# TempControl_PSU.net
KiCad netlist of a schematic drawn in EasyEDA Pro
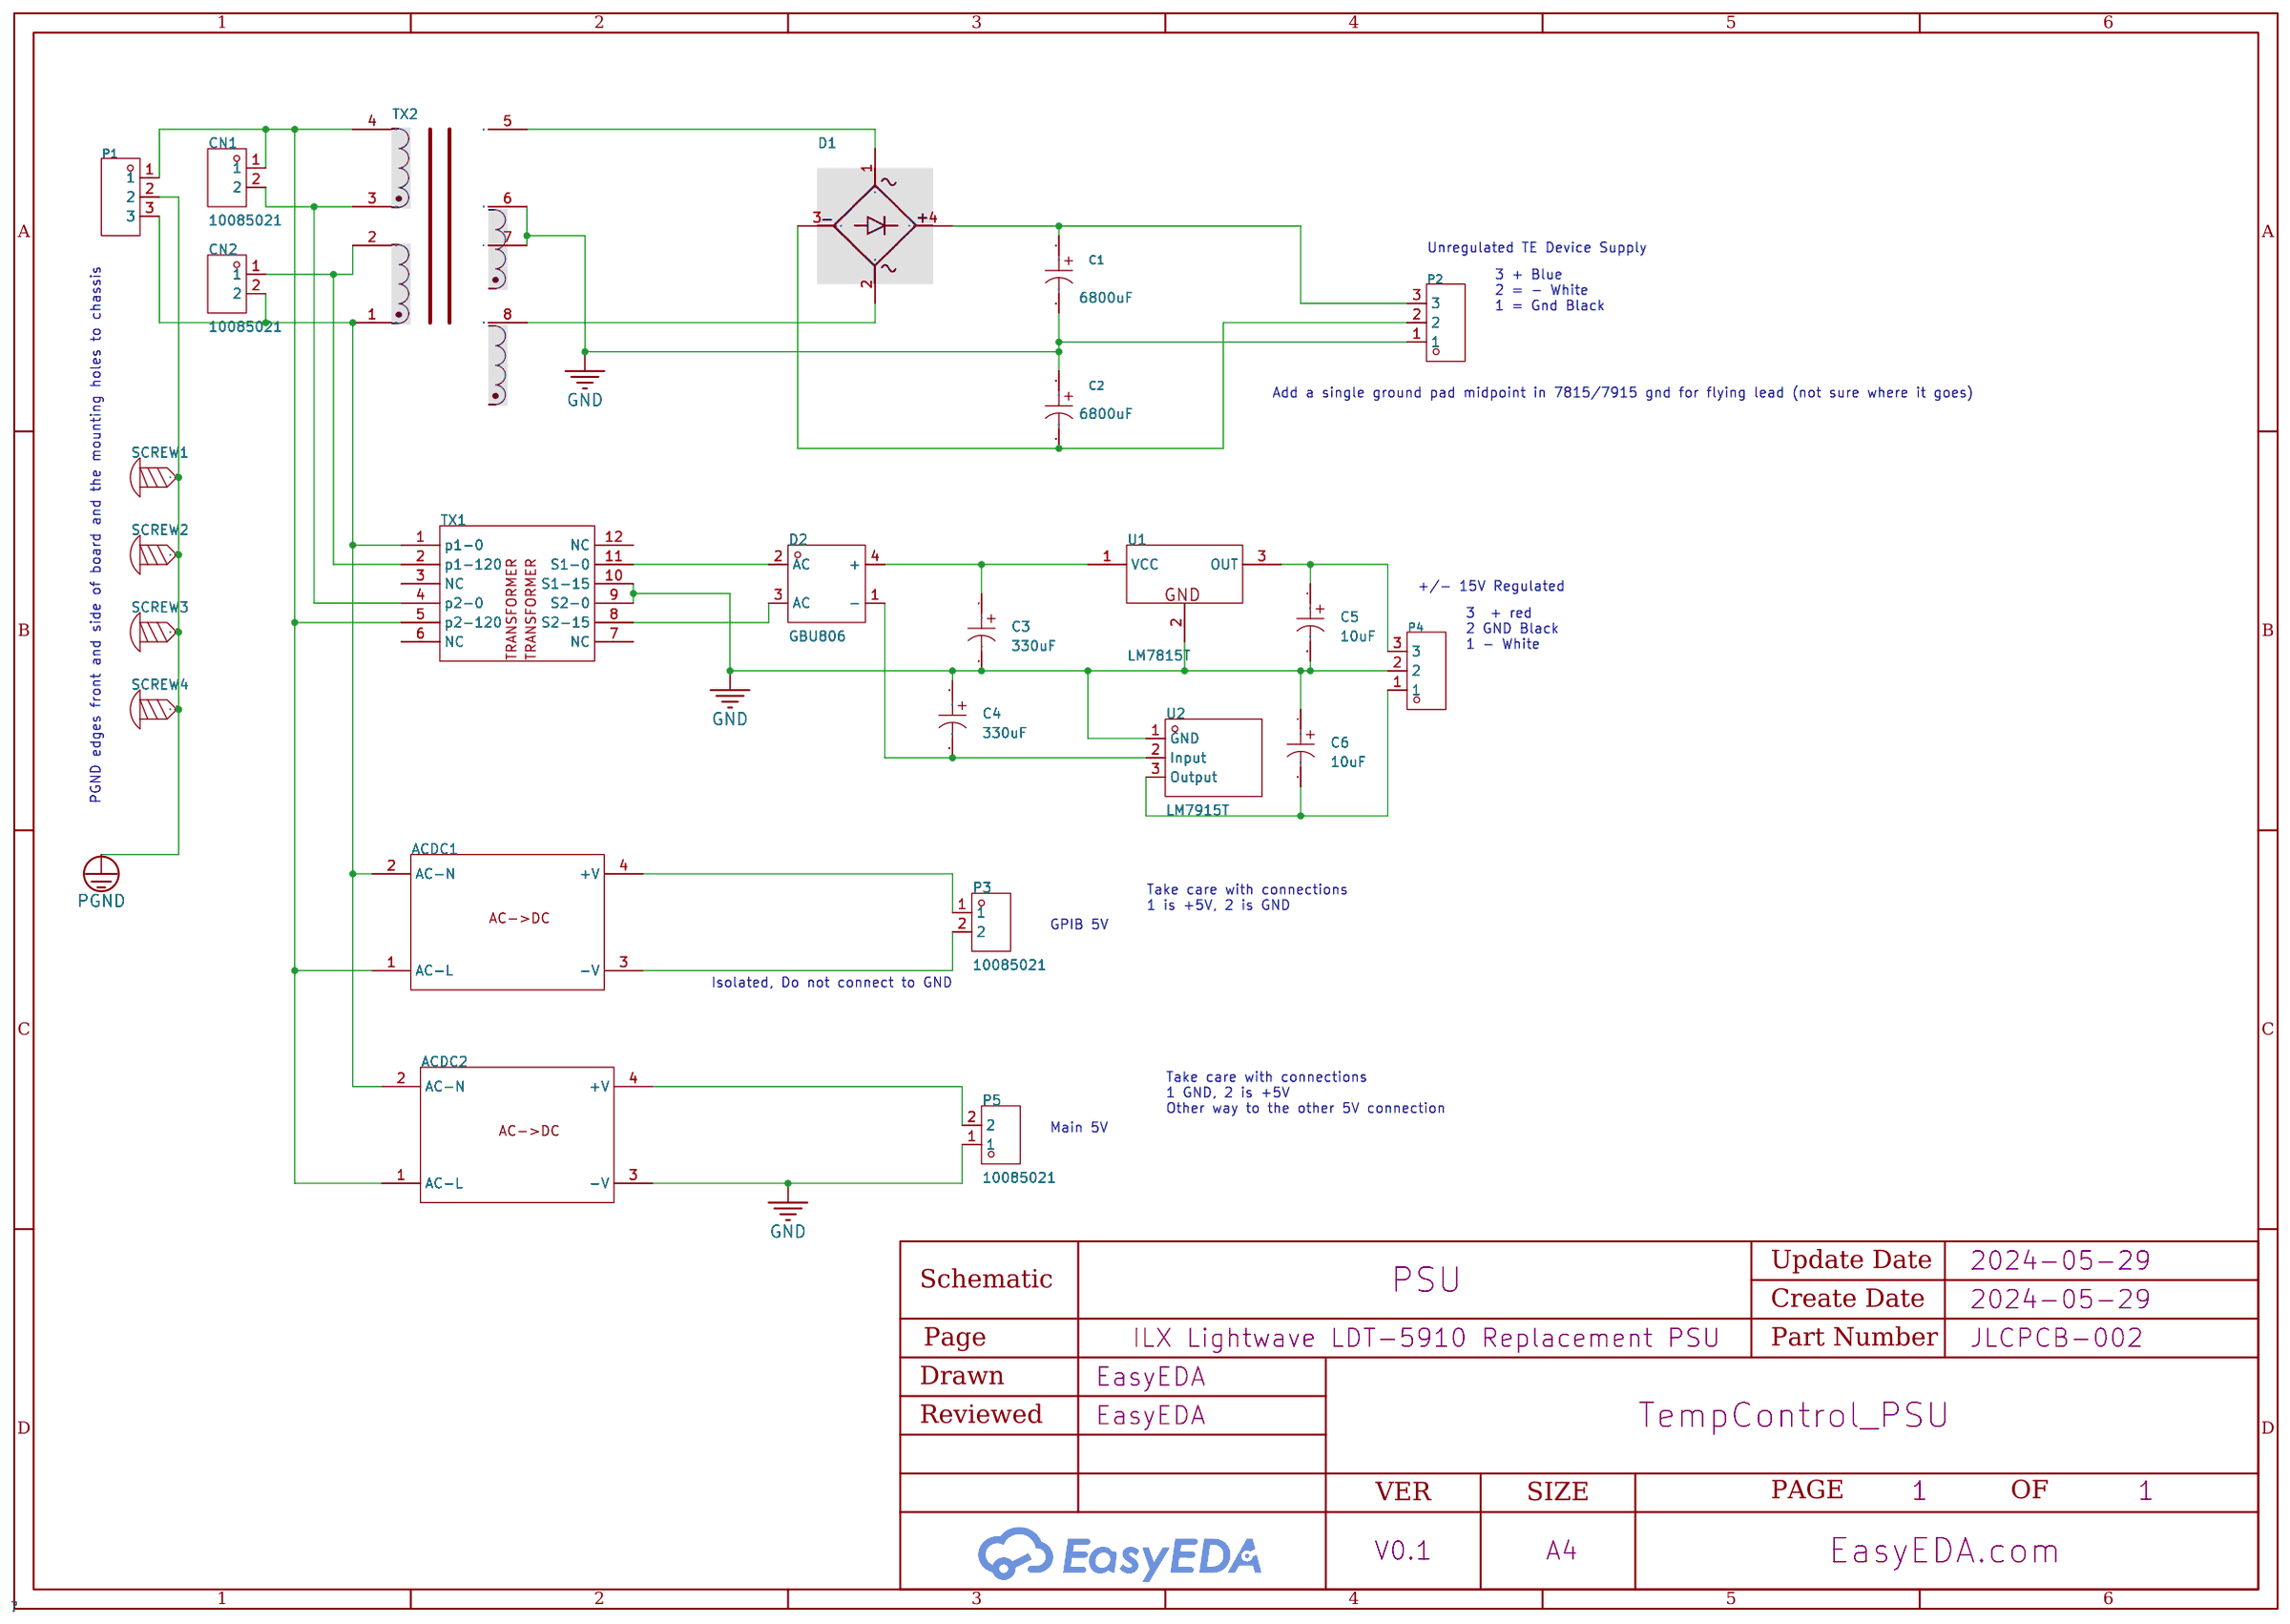
[diagram p0: schematic sheet]

(export (version "E")
  (design (tool "Eeschema 10.0.6"))
  (components
    (comp (ref "ACDC1")
      (value "~")
      (footprint "easyedapro:IRM-05_ACDC_COnverter")
      (description "AC DC Converter")
      (libsource (lib "easyedapro") (part "IRM-05"))
    )
    (comp (ref "ACDC2")
      (value "~")
      (footprint "easyedapro:IRM-05_ACDC_COnverter")
      (description "AC DC Converter")
      (libsource (lib "easyedapro") (part "IRM-05"))
    )
    (comp (ref "C1")
      (value "6800uF")
      (footprint "easyedapro:CAP-TH_BD25.0-P12.00-D1.4-FD")
      (fields (field (name "Manufacturer Part") "UVR1H682MRD6") (field (name "Manufacturer") "Nichicon(尼吉康)"))
      (libsource (lib "easyedapro") (part "UVR1H682MRD6"))
    )
    (comp (ref "C2")
      (value "6800uF")
      (footprint "easyedapro:CAP-TH_BD25.0-P12.00-D1.4-FD")
      (fields (field (name "Manufacturer Part") "UVR1H682MRD6") (field (name "Manufacturer") "Nichicon(尼吉康)"))
      (libsource (lib "easyedapro") (part "UVR1H682MRD6"))
    )
    (comp (ref "C3")
      (value "330uF")
      (footprint "easyedapro:CAP-TH_BD13.0-P5.00-D1.2-FD")
      (fields (field (name "Manufacturer Part") "63V330uF CD288") (field (name "Manufacturer") "HRK(鸿瑞凯电子)"))
      (libsource (lib "easyedapro") (part "63V330UF CD288"))
    )
    (comp (ref "C4")
      (value "330uF")
      (footprint "easyedapro:CAP-TH_BD13.0-P5.00-D1.2-FD")
      (fields (field (name "Manufacturer Part") "63V330uF CD288") (field (name "Manufacturer") "HRK(鸿瑞凯电子)"))
      (libsource (lib "easyedapro") (part "63V330UF CD288"))
    )
    (comp (ref "C5")
      (value "10uF")
      (footprint "easyedapro:CAP-TH_BD5.0-P2.00-D0.5-FD-1")
      (fields
        (field (name "Manufacturer Part") "UPW1H100MDD1TD")
        (field (name "Manufacturer") "Nichicon(尼吉康)")
      )
      (libsource (lib "easyedapro") (part "UPW1H100MDD1TD"))
    )
    (comp (ref "C6")
      (value "10uF")
      (footprint "easyedapro:CAP-TH_BD5.0-P2.00-D0.5-FD-1")
      (fields
        (field (name "Manufacturer Part") "UPW1H100MDD1TD")
        (field (name "Manufacturer") "Nichicon(尼吉康)")
      )
      (libsource (lib "easyedapro") (part "UPW1H100MDD1TD"))
    )
    (comp (ref "CN1")
      (value "10085021")
      (footprint "easyedapro:CONN-TH_P5.08_10085021")
      (fields (field (name "Manufacturer") "MOLEX"))
      (libsource (lib "easyedapro") (part "10085021"))
    )
    (comp (ref "CN2")
      (value "10085021")
      (footprint "easyedapro:CONN-TH_P5.08_10085021")
      (fields (field (name "Manufacturer") "MOLEX"))
      (libsource (lib "easyedapro") (part "10085021"))
    )
    (comp (ref "D1")
      (value "~")
      (footprint "easyedapro:10.8_x 8.2 Square_4-4-Pin")
      (libsource (lib "easyedapro") (part "MB805_Bridge_Rectifier"))
    )
    (comp (ref "D2")
      (value "GBU806")
      (footprint "easyedapro:GBU_4P-L22.0-W3.5-P5.08")
      (fields (field (name "Manufacturer") "DIYI(迪一/芯诺)"))
      (libsource (lib "easyedapro") (part "GBU806_C2440245"))
    )
    (comp (ref "P1")
      (value "HX CH3.96-3P ZZ")
      (footprint "easyedapro:CONN-TH_3P-P3.96_HX-CH3.96-3P-ZZ")
      (fields (field (name "Manufacturer") "hanxia(韩下)"))
      (libsource (lib "easyedapro") (part "HX CH3.96-3P ZZ"))
    )
    (comp (ref "P2")
      (value "HX CH3.96-3P ZZ")
      (footprint "easyedapro:CONN-TH_3P-P3.96_HX-CH3.96-3P-ZZ")
      (fields (field (name "Manufacturer") "hanxia(韩下)"))
      (libsource (lib "easyedapro") (part "HX CH3.96-3P ZZ"))
    )
    (comp (ref "P3")
      (value "10085021")
      (footprint "easyedapro:CONN-TH_P5.08_10085021")
      (fields (field (name "Manufacturer") "MOLEX"))
      (libsource (lib "easyedapro") (part "10085021"))
    )
    (comp (ref "P4")
      (value "HX CH3.96-3P ZZ")
      (footprint "easyedapro:CONN-TH_3P-P3.96_HX-CH3.96-3P-ZZ")
      (fields (field (name "Manufacturer") "hanxia(韩下)"))
      (libsource (lib "easyedapro") (part "HX CH3.96-3P ZZ"))
    )
    (comp (ref "P5")
      (value "10085021")
      (footprint "easyedapro:CONN-TH_P5.08_10085021")
      (fields (field (name "Manufacturer") "MOLEX"))
      (libsource (lib "easyedapro") (part "10085021"))
    )
    (comp (ref "SCREW1")
      (value "~")
      (footprint "easyedapro:Screw-Hole-M2")
      (libsource (lib "easyedapro") (part "Screw-Hole"))
    )
    (comp (ref "SCREW2")
      (value "~")
      (footprint "easyedapro:Screw-Hole-M2")
      (libsource (lib "easyedapro") (part "Screw-Hole"))
    )
    (comp (ref "SCREW3")
      (value "~")
      (footprint "easyedapro:Screw-Hole-M2")
      (libsource (lib "easyedapro") (part "Screw-Hole"))
    )
    (comp (ref "SCREW4")
      (value "~")
      (footprint "easyedapro:Screw-Hole-M2")
      (libsource (lib "easyedapro") (part "Screw-Hole"))
    )
    (comp (ref "TX1")
      (value "~")
      (footprint "easyedapro:EMT474-Transformer")
      (libsource (lib "easyedapro") (part "Transformer 2x15V"))
    )
    (comp (ref "TX2")
      (value "~")
      (footprint "easyedapro:LP-12-3800")
      (libsource (lib "easyedapro") (part "LP-12-3800 Transformer"))
    )
    (comp (ref "U1")
      (value "LM7815T")
      (footprint "easyedapro:TO-220-3_L10.0-W4.5-P2.54-L")
      (description "Output Type:-")
      (fields (field (name "Manufacturer") "HGSEMI(华冠)"))
      (libsource (lib "easyedapro") (part "LM7815T"))
    )
    (comp (ref "U2")
      (value "LM7915T")
      (footprint "easyedapro:TO-220-3_L10.2-W4.5-P2.54-L")
      (description "Output Voltage:15V Output Voltage:15V")
      (fields (field (name "Manufacturer") "HGSEMI(华冠)"))
      (libsource (lib "easyedapro") (part "LM7915T"))
    )
  )
  (nets
    (net (code "1") (name "GND") (class "Default")
      (node (ref "ACDC2") (pin "3") (pinfunction "-V_3") (pintype "bidirectional"))
      (node (ref "C1") (pin "2") (pinfunction "2_2") (pintype "input"))
      (node (ref "C2") (pin "1") (pinfunction "1_1") (pintype "input"))
      (node (ref "C3") (pin "2") (pinfunction "2_2") (pintype "input"))
      (node (ref "C4") (pin "1") (pinfunction "1_1") (pintype "input"))
      (node (ref "C5") (pin "2") (pinfunction "2_2") (pintype "input"))
      (node (ref "C6") (pin "1") (pinfunction "1_1") (pintype "input"))
      (node (ref "P2") (pin "1") (pinfunction "1_1") (pintype "input"))
      (node (ref "P4") (pin "2") (pinfunction "2_2") (pintype "input"))
      (node (ref "P5") (pin "1") (pinfunction "1_1") (pintype "unspecified"))
      (node (ref "TX1") (pin "10") (pinfunction "S1-15_10") (pintype "bidirectional"))
      (node (ref "TX1") (pin "9") (pinfunction "S2-0_9") (pintype "bidirectional"))
      (node (ref "TX2") (pin "6") (pinfunction "6_6") (pintype "input"))
      (node (ref "TX2") (pin "7") (pinfunction "7_7") (pintype "bidirectional"))
      (node (ref "U1") (pin "2") (pinfunction "GND_2") (pintype "input"))
      (node (ref "U2") (pin "1") (pinfunction "GND_1") (pintype "input"))
    )
    (net (code "2") (name "Net-(ACDC1-+V)") (class "Default")
      (node (ref "ACDC1") (pin "4") (pinfunction "+V_4") (pintype "bidirectional"))
      (node (ref "P3") (pin "1") (pinfunction "1_1") (pintype "unspecified"))
    )
    (net (code "3") (name "Net-(ACDC1--V)") (class "Default")
      (node (ref "ACDC1") (pin "3") (pinfunction "-V_3") (pintype "bidirectional"))
      (node (ref "P3") (pin "2") (pinfunction "2_2") (pintype "unspecified"))
    )
    (net (code "4") (name "Net-(ACDC1-AC-L)") (class "Default")
      (node (ref "ACDC1") (pin "1") (pinfunction "AC-L_1") (pintype "bidirectional"))
      (node (ref "ACDC2") (pin "1") (pinfunction "AC-L_1") (pintype "bidirectional"))
      (node (ref "CN1") (pin "1") (pinfunction "1_1") (pintype "unspecified"))
      (node (ref "P1") (pin "1") (pinfunction "1_1") (pintype "input"))
      (node (ref "TX1") (pin "5") (pinfunction "p2-120_5") (pintype "bidirectional"))
      (node (ref "TX2") (pin "4") (pinfunction "4_4") (pintype "input"))
    )
    (net (code "5") (name "Net-(ACDC1-AC-N)") (class "Default")
      (node (ref "ACDC1") (pin "2") (pinfunction "AC-N_2") (pintype "bidirectional"))
      (node (ref "ACDC2") (pin "2") (pinfunction "AC-N_2") (pintype "bidirectional"))
      (node (ref "CN2") (pin "2") (pinfunction "2_2") (pintype "unspecified"))
      (node (ref "P1") (pin "3") (pinfunction "3_3") (pintype "input"))
      (node (ref "TX1") (pin "1") (pinfunction "p1-0_1") (pintype "bidirectional"))
      (node (ref "TX2") (pin "1") (pinfunction "1_1") (pintype "input"))
    )
    (net (code "6") (name "Net-(ACDC2-+V)") (class "Default")
      (node (ref "ACDC2") (pin "4") (pinfunction "+V_4") (pintype "bidirectional"))
      (node (ref "P5") (pin "2") (pinfunction "2_2") (pintype "unspecified"))
    )
    (net (code "7") (name "Net-(C1-Pad1)") (class "Default")
      (node (ref "C1") (pin "1") (pinfunction "1_1") (pintype "input"))
      (node (ref "D1") (pin "4") (pinfunction "4_4") (pintype "input"))
      (node (ref "P2") (pin "3") (pinfunction "3_3") (pintype "input"))
    )
    (net (code "8") (name "Net-(C2-Pad2)") (class "Default")
      (node (ref "C2") (pin "2") (pinfunction "2_2") (pintype "input"))
      (node (ref "D1") (pin "3") (pinfunction "3_3") (pintype "input"))
      (node (ref "P2") (pin "2") (pinfunction "2_2") (pintype "input"))
    )
    (net (code "9") (name "Net-(D1-Pad1)") (class "Default")
      (node (ref "D1") (pin "1") (pinfunction "1_1") (pintype "input"))
      (node (ref "TX2") (pin "5") (pinfunction "5_5") (pintype "input"))
    )
    (net (code "10") (name "Net-(D1-Pad2)") (class "Default")
      (node (ref "D1") (pin "2") (pinfunction "2_2") (pintype "input"))
      (node (ref "TX2") (pin "8") (pinfunction "8_8") (pintype "input"))
    )
    (net (code "11") (name "Net-(D2-+)") (class "Default")
      (node (ref "C3") (pin "1") (pinfunction "1_1") (pintype "input"))
      (node (ref "D2") (pin "4") (pinfunction "+_4") (pintype "unspecified"))
      (node (ref "U1") (pin "1") (pinfunction "VCC_1") (pintype "input"))
    )
    (net (code "12") (name "Net-(D2--)") (class "Default")
      (node (ref "C4") (pin "2") (pinfunction "2_2") (pintype "input"))
      (node (ref "D2") (pin "1") (pinfunction "-_1") (pintype "unspecified"))
      (node (ref "U2") (pin "2") (pinfunction "Input_2") (pintype "input"))
    )
    (net (code "13") (name "Net-(TX1-S1-0)") (class "Default")
      (node (ref "D2") (pin "2") (pinfunction "AC_2") (pintype "unspecified"))
      (node (ref "TX1") (pin "11") (pinfunction "S1-0_11") (pintype "bidirectional"))
    )
    (net (code "14") (name "Net-(TX1-S2-15)") (class "Default")
      (node (ref "D2") (pin "3") (pinfunction "AC_3") (pintype "unspecified"))
      (node (ref "TX1") (pin "8") (pinfunction "S2-15_8") (pintype "bidirectional"))
    )
    (net (code "15") (name "Net-(TX1-p1-120)") (class "Default")
      (node (ref "CN2") (pin "1") (pinfunction "1_1") (pintype "unspecified"))
      (node (ref "TX1") (pin "2") (pinfunction "p1-120_2") (pintype "bidirectional"))
      (node (ref "TX2") (pin "2") (pinfunction "2_2") (pintype "input"))
    )
    (net (code "16") (name "Net-(TX1-p2-0)") (class "Default")
      (node (ref "CN1") (pin "2") (pinfunction "2_2") (pintype "unspecified"))
      (node (ref "TX1") (pin "4") (pinfunction "p2-0_4") (pintype "bidirectional"))
      (node (ref "TX2") (pin "3") (pinfunction "3_3") (pintype "input"))
    )
    (net (code "17") (name "Net-(U1-OUT)") (class "Default")
      (node (ref "C5") (pin "1") (pinfunction "1_1") (pintype "input"))
      (node (ref "P4") (pin "3") (pinfunction "3_3") (pintype "input"))
      (node (ref "U1") (pin "3") (pinfunction "OUT_3") (pintype "input"))
    )
    (net (code "18") (name "Net-(U2-Output)") (class "Default")
      (node (ref "C6") (pin "2") (pinfunction "2_2") (pintype "input"))
      (node (ref "P4") (pin "1") (pinfunction "1_1") (pintype "input"))
      (node (ref "U2") (pin "3") (pinfunction "Output_3") (pintype "input"))
    )
    (net (code "19") (name "PGND") (class "Default")
      (node (ref "P1") (pin "2") (pinfunction "2_2") (pintype "input"))
      (node (ref "SCREW1") (pin "1") (pinfunction "1_1") (pintype "input"))
      (node (ref "SCREW2") (pin "1") (pinfunction "1_1") (pintype "input"))
      (node (ref "SCREW3") (pin "1") (pinfunction "1_1") (pintype "input"))
      (node (ref "SCREW4") (pin "1") (pinfunction "1_1") (pintype "input"))
    )
    (net (code "20") (name "unconnected-(TX1-NC-Pad3)") (class "Default")
      (node (ref "TX1") (pin "3") (pinfunction "NC_3") (pintype "bidirectional"))
    )
    (net (code "21") (name "unconnected-(TX1-NC-Pad6)") (class "Default")
      (node (ref "TX1") (pin "6") (pinfunction "NC_6") (pintype "bidirectional"))
    )
    (net (code "22") (name "unconnected-(TX1-NC-Pad7)") (class "Default")
      (node (ref "TX1") (pin "7") (pinfunction "NC_7") (pintype "bidirectional"))
    )
    (net (code "23") (name "unconnected-(TX1-NC-Pad12)") (class "Default")
      (node (ref "TX1") (pin "12") (pinfunction "NC_12") (pintype "bidirectional"))
    )
  )
)
